# MotorController.net
KiCad netlist of a schematic drawn in Altium Designer
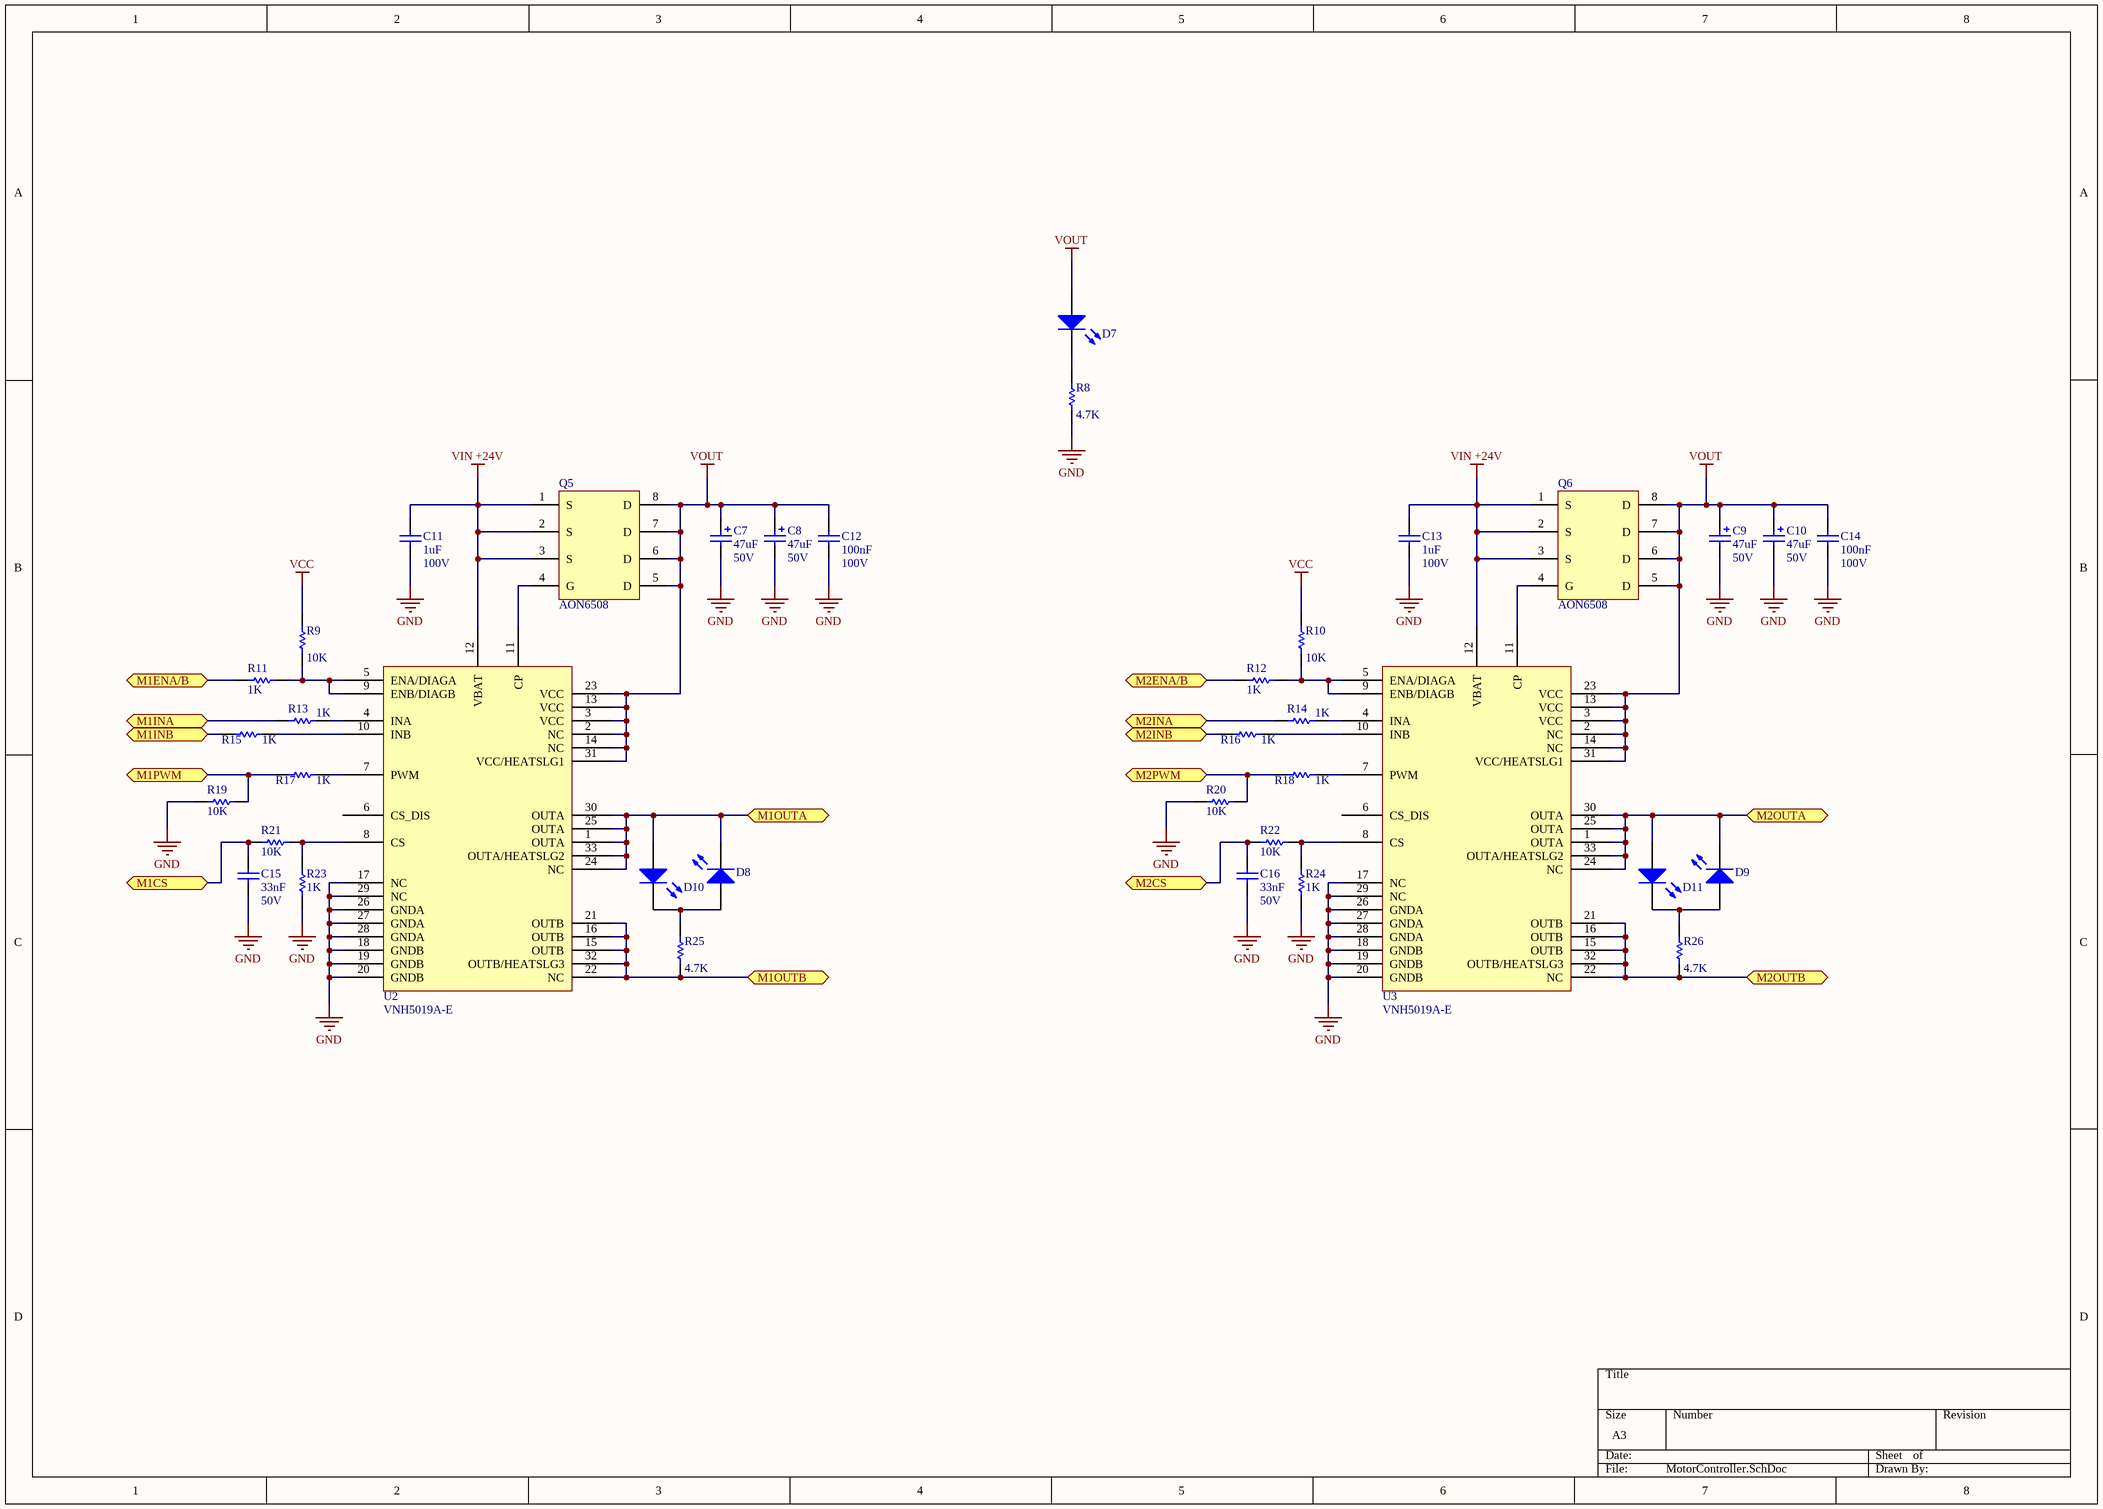
[diagram p0: MotorController.SchDoc]

(export (version "E")
  (design (tool "Eeschema 10.0.6"))
  (components
    (comp (ref "C7")
      (value "47uF")
      (footprint "CAP D Size")
      (description "Polarized Capacitor (Radial)")
      (fields
        (field (name "VOLTAGE") "50V")
        (field (name "Comment") "Cap Pol1")
        (field (name "PUBLISHER") "Altium Limited")
      )
      (libsource (lib "Erdem_05112012") (part "Cap Pol1"))
    )
    (comp (ref "C8")
      (value "47uF")
      (footprint "CAP D Size")
      (description "Polarized Capacitor (Radial)")
      (fields
        (field (name "VOLTAGE") "50V")
        (field (name "Comment") "Cap Pol1")
        (field (name "PUBLISHER") "Altium Limited")
      )
      (libsource (lib "Erdem_05112012") (part "Cap Pol1"))
    )
    (comp (ref "C9")
      (value "47uF")
      (footprint "CAP D Size")
      (description "Polarized Capacitor (Radial)")
      (fields
        (field (name "VOLTAGE") "50V")
        (field (name "Comment") "Cap Pol1")
        (field (name "PUBLISHER") "Altium Limited")
      )
      (libsource (lib "Erdem_05112012") (part "Cap Pol1"))
    )
    (comp (ref "C10")
      (value "47uF")
      (footprint "CAP D Size")
      (description "Polarized Capacitor (Radial)")
      (fields
        (field (name "VOLTAGE") "50V")
        (field (name "Comment") "Cap Pol1")
        (field (name "PUBLISHER") "Altium Limited")
      )
      (libsource (lib "Erdem_05112012") (part "Cap Pol1"))
    )
    (comp (ref "C11")
      (value "1uF")
      (footprint "8-1206")
      (description "Capacitor")
      (fields
        (field (name "VOLTAGE") "100V")
        (field (name "Comment") "Cap")
        (field (name "PUBLISHER") "Altium Limited")
      )
      (libsource (lib "Erdem_05112012") (part "Cap"))
    )
    (comp (ref "C12")
      (value "100nF")
      (footprint "6-0805 - big")
      (description "Capacitor")
      (fields
        (field (name "VOLTAGE") "100V")
        (field (name "Comment") "Cap")
        (field (name "PUBLISHER") "Altium Limited")
      )
      (libsource (lib "Erdem_05112012") (part "Cap"))
    )
    (comp (ref "C13")
      (value "1uF")
      (footprint "8-1206")
      (description "Capacitor")
      (fields
        (field (name "VOLTAGE") "100V")
        (field (name "Comment") "Cap")
        (field (name "PUBLISHER") "Altium Limited")
      )
      (libsource (lib "Erdem_05112012") (part "Cap"))
    )
    (comp (ref "C14")
      (value "100nF")
      (footprint "6-0805 - big")
      (description "Capacitor")
      (fields
        (field (name "VOLTAGE") "100V")
        (field (name "Comment") "Cap")
        (field (name "PUBLISHER") "Altium Limited")
      )
      (libsource (lib "Erdem_05112012") (part "Cap"))
    )
    (comp (ref "C15")
      (value "33nF")
      (footprint "3-0603_L")
      (description "Capacitor")
      (fields
        (field (name "VOLTAGE") "50V")
        (field (name "Comment") "Cap")
        (field (name "PUBLISHER") "Altium Limited")
      )
      (libsource (lib "Erdem_05112012") (part "Cap"))
    )
    (comp (ref "C16")
      (value "33nF")
      (footprint "3-0603_L")
      (description "Capacitor")
      (fields
        (field (name "VOLTAGE") "50V")
        (field (name "Comment") "Cap")
        (field (name "PUBLISHER") "Altium Limited")
      )
      (libsource (lib "Erdem_05112012") (part "Cap"))
    )
    (comp (ref "D7")
      (value "LED")
      (footprint "6-0805 - LED")
      (description "Typical INFRARED GaAs LED")
      (fields (field (name "PUBLISHER") "Altium Limited"))
      (libsource (lib "Erdem_05112012") (part "LED"))
    )
    (comp (ref "D8")
      (value "LED")
      (footprint "6-0805 - LED")
      (description "Typical INFRARED GaAs LED")
      (fields (field (name "PUBLISHER") "Altium Limited"))
      (libsource (lib "Erdem_05112012") (part "LED"))
    )
    (comp (ref "D9")
      (value "LED")
      (footprint "6-0805 - LED")
      (description "Typical INFRARED GaAs LED")
      (fields (field (name "PUBLISHER") "Altium Limited"))
      (libsource (lib "Erdem_05112012") (part "LED"))
    )
    (comp (ref "D10")
      (value "LED")
      (footprint "6-0805 - LED")
      (description "Typical INFRARED GaAs LED")
      (fields (field (name "PUBLISHER") "Altium Limited"))
      (libsource (lib "Erdem_05112012") (part "LED"))
    )
    (comp (ref "D11")
      (value "LED")
      (footprint "6-0805 - LED")
      (description "Typical INFRARED GaAs LED")
      (fields (field (name "PUBLISHER") "Altium Limited"))
      (libsource (lib "Erdem_05112012") (part "LED"))
    )
    (comp (ref "Q5")
      (value "AON6508")
      (footprint "DFN5x6 EP")
      (description "30V N-Channel AlphaMOS")
      (fields (field (name "PUBLISHER") "Altium Limited"))
      (libsource (lib "Erdem_05112012") (part "AON6508"))
    )
    (comp (ref "Q6")
      (value "AON6508")
      (footprint "DFN5x6 EP")
      (description "30V N-Channel AlphaMOS")
      (fields (field (name "PUBLISHER") "Altium Limited"))
      (libsource (lib "Erdem_05112012") (part "AON6508"))
    )
    (comp (ref "R8")
      (value "4.7K")
      (footprint "3-0603_L")
      (description "Resistor")
      (fields (field (name "Comment") "Res1") (field (name "PUBLISHER") "Altium Limited"))
      (libsource (lib "Erdem_05112012") (part "Res1"))
    )
    (comp (ref "R9")
      (value "10K")
      (footprint "3-0603_L")
      (description "Resistor")
      (fields (field (name "Comment") "Res1") (field (name "PUBLISHER") "Altium Limited"))
      (libsource (lib "Erdem_05112012") (part "Res1"))
    )
    (comp (ref "R10")
      (value "10K")
      (footprint "3-0603_L")
      (description "Resistor")
      (fields (field (name "Comment") "Res1") (field (name "PUBLISHER") "Altium Limited"))
      (libsource (lib "Erdem_05112012") (part "Res1"))
    )
    (comp (ref "R11")
      (value "1K")
      (footprint "3-0603_L")
      (description "Resistor")
      (fields (field (name "Comment") "Res1") (field (name "PUBLISHER") "Altium Limited"))
      (libsource (lib "Erdem_05112012") (part "Res1"))
    )
    (comp (ref "R12")
      (value "1K")
      (footprint "3-0603_L")
      (description "Resistor")
      (fields (field (name "Comment") "Res1") (field (name "PUBLISHER") "Altium Limited"))
      (libsource (lib "Erdem_05112012") (part "Res1"))
    )
    (comp (ref "R13")
      (value "1K")
      (footprint "3-0603_L")
      (description "Resistor")
      (fields (field (name "Comment") "Res1") (field (name "PUBLISHER") "Altium Limited"))
      (libsource (lib "Erdem_05112012") (part "Res1"))
    )
    (comp (ref "R14")
      (value "1K")
      (footprint "3-0603_L")
      (description "Resistor")
      (fields (field (name "Comment") "Res1") (field (name "PUBLISHER") "Altium Limited"))
      (libsource (lib "Erdem_05112012") (part "Res1"))
    )
    (comp (ref "R15")
      (value "1K")
      (footprint "3-0603_L")
      (description "Resistor")
      (fields (field (name "Comment") "Res1") (field (name "PUBLISHER") "Altium Limited"))
      (libsource (lib "Erdem_05112012") (part "Res1"))
    )
    (comp (ref "R16")
      (value "1K")
      (footprint "3-0603_L")
      (description "Resistor")
      (fields (field (name "Comment") "Res1") (field (name "PUBLISHER") "Altium Limited"))
      (libsource (lib "Erdem_05112012") (part "Res1"))
    )
    (comp (ref "R17")
      (value "1K")
      (footprint "3-0603_L")
      (description "Resistor")
      (fields (field (name "Comment") "Res1") (field (name "PUBLISHER") "Altium Limited"))
      (libsource (lib "Erdem_05112012") (part "Res1"))
    )
    (comp (ref "R18")
      (value "1K")
      (footprint "3-0603_L")
      (description "Resistor")
      (fields (field (name "Comment") "Res1") (field (name "PUBLISHER") "Altium Limited"))
      (libsource (lib "Erdem_05112012") (part "Res1"))
    )
    (comp (ref "R19")
      (value "10K")
      (footprint "3-0603_L")
      (description "Resistor")
      (fields (field (name "Comment") "Res1") (field (name "PUBLISHER") "Altium Limited"))
      (libsource (lib "Erdem_05112012") (part "Res1"))
    )
    (comp (ref "R20")
      (value "10K")
      (footprint "3-0603_L")
      (description "Resistor")
      (fields (field (name "Comment") "Res1") (field (name "PUBLISHER") "Altium Limited"))
      (libsource (lib "Erdem_05112012") (part "Res1"))
    )
    (comp (ref "R21")
      (value "10K")
      (footprint "3-0603_L")
      (description "Resistor")
      (fields (field (name "Comment") "Res1") (field (name "PUBLISHER") "Altium Limited"))
      (libsource (lib "Erdem_05112012") (part "Res1"))
    )
    (comp (ref "R22")
      (value "10K")
      (footprint "3-0603_L")
      (description "Resistor")
      (fields (field (name "Comment") "Res1") (field (name "PUBLISHER") "Altium Limited"))
      (libsource (lib "Erdem_05112012") (part "Res1"))
    )
    (comp (ref "R23")
      (value "1K")
      (footprint "3-0603_L")
      (description "Resistor")
      (fields (field (name "Comment") "Res1") (field (name "PUBLISHER") "Altium Limited"))
      (libsource (lib "Erdem_05112012") (part "Res1"))
    )
    (comp (ref "R24")
      (value "1K")
      (footprint "3-0603_L")
      (description "Resistor")
      (fields (field (name "Comment") "Res1") (field (name "PUBLISHER") "Altium Limited"))
      (libsource (lib "Erdem_05112012") (part "Res1"))
    )
    (comp (ref "R25")
      (value "4.7K")
      (footprint "3-0603_L")
      (description "Resistor")
      (fields (field (name "Comment") "Res1") (field (name "PUBLISHER") "Altium Limited"))
      (libsource (lib "Erdem_05112012") (part "Res1"))
    )
    (comp (ref "R26")
      (value "4.7K")
      (footprint "3-0603_L")
      (description "Resistor")
      (fields (field (name "Comment") "Res1") (field (name "PUBLISHER") "Altium Limited"))
      (libsource (lib "Erdem_05112012") (part "Res1"))
    )
    (comp (ref "U2")
      (value "VNH5019A-E")
      (footprint "MultiPowerSO-30")
      (description "Automotive fully integrated H-bridge motor driver")
      (fields (field (name "PUBLISHER") "Altium Limited"))
      (libsource (lib "Erdem_05112012") (part "VNH5019A-E"))
    )
    (comp (ref "U3")
      (value "VNH5019A-E")
      (footprint "MultiPowerSO-30")
      (description "Automotive fully integrated H-bridge motor driver")
      (fields (field (name "PUBLISHER") "Altium Limited"))
      (libsource (lib "Erdem_05112012") (part "VNH5019A-E"))
    )
  )
  (nets
    (net (code "1") (name "/M1CS") (class "Default")
      (node (ref "C15") (pin "2") (pinfunction "2_2") (pintype "passive"))
      (node (ref "R21") (pin "2") (pinfunction "2_2") (pintype "passive"))
    )
    (net (code "2") (name "/M1ENA{slash}B") (class "Default")
      (node (ref "R11") (pin "1") (pinfunction "1_1") (pintype "passive"))
    )
    (net (code "3") (name "/M1INA") (class "Default")
      (node (ref "R13") (pin "1") (pinfunction "1_1") (pintype "passive"))
    )
    (net (code "4") (name "/M1INB") (class "Default")
      (node (ref "R15") (pin "1") (pinfunction "1_1") (pintype "passive"))
    )
    (net (code "5") (name "/M1OUTA") (class "Default")
      (node (ref "D10") (pin "1") (pinfunction "A_1") (pintype "passive"))
      (node (ref "D8") (pin "2") (pinfunction "K_2") (pintype "passive"))
      (node (ref "U2") (pin "1") (pinfunction "OUTA_1") (pintype "passive"))
      (node (ref "U2") (pin "24") (pinfunction "NC_24") (pintype "passive"))
      (node (ref "U2") (pin "25") (pinfunction "OUTA_25") (pintype "passive"))
      (node (ref "U2") (pin "30") (pinfunction "OUTA_30") (pintype "passive"))
      (node (ref "U2") (pin "33") (pinfunction "OUTA/HEATSLG2_33") (pintype "passive"))
    )
    (net (code "6") (name "/M1OUTB") (class "Default")
      (node (ref "R25") (pin "1") (pinfunction "1_1") (pintype "passive"))
      (node (ref "U2") (pin "15") (pinfunction "OUTB_15") (pintype "passive"))
      (node (ref "U2") (pin "16") (pinfunction "OUTB_16") (pintype "passive"))
      (node (ref "U2") (pin "21") (pinfunction "OUTB_21") (pintype "passive"))
      (node (ref "U2") (pin "22") (pinfunction "NC_22") (pintype "passive"))
      (node (ref "U2") (pin "32") (pinfunction "OUTB/HEATSLG3_32") (pintype "passive"))
    )
    (net (code "7") (name "/M1PWM") (class "Default")
      (node (ref "R17") (pin "1") (pinfunction "1_1") (pintype "passive"))
      (node (ref "R19") (pin "2") (pinfunction "2_2") (pintype "passive"))
    )
    (net (code "8") (name "/M2CS") (class "Default")
      (node (ref "C16") (pin "2") (pinfunction "2_2") (pintype "passive"))
      (node (ref "R22") (pin "2") (pinfunction "2_2") (pintype "passive"))
    )
    (net (code "9") (name "/M2ENA{slash}B") (class "Default")
      (node (ref "R12") (pin "1") (pinfunction "1_1") (pintype "passive"))
    )
    (net (code "10") (name "/M2INA") (class "Default")
      (node (ref "R14") (pin "1") (pinfunction "1_1") (pintype "passive"))
    )
    (net (code "11") (name "/M2INB") (class "Default")
      (node (ref "R16") (pin "1") (pinfunction "1_1") (pintype "passive"))
    )
    (net (code "12") (name "/M2OUTA") (class "Default")
      (node (ref "D11") (pin "1") (pinfunction "A_1") (pintype "passive"))
      (node (ref "D9") (pin "2") (pinfunction "K_2") (pintype "passive"))
      (node (ref "U3") (pin "1") (pinfunction "OUTA_1") (pintype "passive"))
      (node (ref "U3") (pin "24") (pinfunction "NC_24") (pintype "passive"))
      (node (ref "U3") (pin "25") (pinfunction "OUTA_25") (pintype "passive"))
      (node (ref "U3") (pin "30") (pinfunction "OUTA_30") (pintype "passive"))
      (node (ref "U3") (pin "33") (pinfunction "OUTA/HEATSLG2_33") (pintype "passive"))
    )
    (net (code "13") (name "/M2OUTB") (class "Default")
      (node (ref "R26") (pin "1") (pinfunction "1_1") (pintype "passive"))
      (node (ref "U3") (pin "15") (pinfunction "OUTB_15") (pintype "passive"))
      (node (ref "U3") (pin "16") (pinfunction "OUTB_16") (pintype "passive"))
      (node (ref "U3") (pin "21") (pinfunction "OUTB_21") (pintype "passive"))
      (node (ref "U3") (pin "22") (pinfunction "NC_22") (pintype "passive"))
      (node (ref "U3") (pin "32") (pinfunction "OUTB/HEATSLG3_32") (pintype "passive"))
    )
    (net (code "14") (name "/M2PWM") (class "Default")
      (node (ref "R18") (pin "1") (pinfunction "1_1") (pintype "passive"))
      (node (ref "R20") (pin "2") (pinfunction "2_2") (pintype "passive"))
    )
    (net (code "15") (name "GND") (class "Default")
      (node (ref "C10") (pin "2") (pinfunction "2_2") (pintype "passive"))
      (node (ref "C11") (pin "1") (pinfunction "1_1") (pintype "passive"))
      (node (ref "C12") (pin "1") (pinfunction "1_1") (pintype "passive"))
      (node (ref "C13") (pin "1") (pinfunction "1_1") (pintype "passive"))
      (node (ref "C14") (pin "1") (pinfunction "1_1") (pintype "passive"))
      (node (ref "C15") (pin "1") (pinfunction "1_1") (pintype "passive"))
      (node (ref "C16") (pin "1") (pinfunction "1_1") (pintype "passive"))
      (node (ref "C7") (pin "2") (pinfunction "2_2") (pintype "passive"))
      (node (ref "C8") (pin "2") (pinfunction "2_2") (pintype "passive"))
      (node (ref "C9") (pin "2") (pinfunction "2_2") (pintype "passive"))
      (node (ref "R19") (pin "1") (pinfunction "1_1") (pintype "passive"))
      (node (ref "R20") (pin "1") (pinfunction "1_1") (pintype "passive"))
      (node (ref "R23") (pin "1") (pinfunction "1_1") (pintype "passive"))
      (node (ref "R24") (pin "1") (pinfunction "1_1") (pintype "passive"))
      (node (ref "R8") (pin "1") (pinfunction "1_1") (pintype "passive"))
      (node (ref "U2") (pin "17") (pinfunction "NC_17") (pintype "passive"))
      (node (ref "U2") (pin "18") (pinfunction "GNDB_18") (pintype "passive"))
      (node (ref "U2") (pin "19") (pinfunction "GNDB_19") (pintype "passive"))
      (node (ref "U2") (pin "20") (pinfunction "GNDB_20") (pintype "passive"))
      (node (ref "U2") (pin "26") (pinfunction "GNDA_26") (pintype "passive"))
      (node (ref "U2") (pin "27") (pinfunction "GNDA_27") (pintype "passive"))
      (node (ref "U2") (pin "28") (pinfunction "GNDA_28") (pintype "passive"))
      (node (ref "U2") (pin "29") (pinfunction "NC_29") (pintype "passive"))
      (node (ref "U3") (pin "17") (pinfunction "NC_17") (pintype "passive"))
      (node (ref "U3") (pin "18") (pinfunction "GNDB_18") (pintype "passive"))
      (node (ref "U3") (pin "19") (pinfunction "GNDB_19") (pintype "passive"))
      (node (ref "U3") (pin "20") (pinfunction "GNDB_20") (pintype "passive"))
      (node (ref "U3") (pin "26") (pinfunction "GNDA_26") (pintype "passive"))
      (node (ref "U3") (pin "27") (pinfunction "GNDA_27") (pintype "passive"))
      (node (ref "U3") (pin "28") (pinfunction "GNDA_28") (pintype "passive"))
      (node (ref "U3") (pin "29") (pinfunction "NC_29") (pintype "passive"))
    )
    (net (code "16") (name "Net-(D7-K)") (class "Default")
      (node (ref "D7") (pin "2") (pinfunction "K_2") (pintype "passive"))
      (node (ref "R8") (pin "2") (pinfunction "2_2") (pintype "passive"))
    )
    (net (code "17") (name "Net-(D10-K)") (class "Default")
      (node (ref "D10") (pin "2") (pinfunction "K_2") (pintype "passive"))
      (node (ref "D8") (pin "1") (pinfunction "A_1") (pintype "passive"))
      (node (ref "R25") (pin "2") (pinfunction "2_2") (pintype "passive"))
    )
    (net (code "18") (name "Net-(D11-K)") (class "Default")
      (node (ref "D11") (pin "2") (pinfunction "K_2") (pintype "passive"))
      (node (ref "D9") (pin "1") (pinfunction "A_1") (pintype "passive"))
      (node (ref "R26") (pin "2") (pinfunction "2_2") (pintype "passive"))
    )
    (net (code "19") (name "Net-(Q5-G)") (class "Default")
      (node (ref "Q5") (pin "4") (pinfunction "G_4") (pintype "passive"))
      (node (ref "U2") (pin "11") (pinfunction "CP_11") (pintype "passive"))
    )
    (net (code "20") (name "Net-(Q6-G)") (class "Default")
      (node (ref "Q6") (pin "4") (pinfunction "G_4") (pintype "passive"))
      (node (ref "U3") (pin "11") (pinfunction "CP_11") (pintype "passive"))
    )
    (net (code "21") (name "Net-(U2-CS)") (class "Default")
      (node (ref "R21") (pin "1") (pinfunction "1_1") (pintype "passive"))
      (node (ref "R23") (pin "2") (pinfunction "2_2") (pintype "passive"))
      (node (ref "U2") (pin "8") (pinfunction "CS_8") (pintype "passive"))
    )
    (net (code "22") (name "Net-(U2-ENA{slash}DIAGA)") (class "Default")
      (node (ref "R11") (pin "2") (pinfunction "2_2") (pintype "passive"))
      (node (ref "R9") (pin "1") (pinfunction "1_1") (pintype "passive"))
      (node (ref "U2") (pin "5") (pinfunction "ENA/DIAGA_5") (pintype "passive"))
      (node (ref "U2") (pin "9") (pinfunction "ENB/DIAGB_9") (pintype "passive"))
    )
    (net (code "23") (name "Net-(U2-INA)") (class "Default")
      (node (ref "R13") (pin "2") (pinfunction "2_2") (pintype "passive"))
      (node (ref "U2") (pin "4") (pinfunction "INA_4") (pintype "passive"))
    )
    (net (code "24") (name "Net-(U2-INB)") (class "Default")
      (node (ref "R15") (pin "2") (pinfunction "2_2") (pintype "passive"))
      (node (ref "U2") (pin "10") (pinfunction "INB_10") (pintype "passive"))
    )
    (net (code "25") (name "Net-(U2-PWM)") (class "Default")
      (node (ref "R17") (pin "2") (pinfunction "2_2") (pintype "passive"))
      (node (ref "U2") (pin "7") (pinfunction "PWM_7") (pintype "passive"))
    )
    (net (code "26") (name "Net-(U3-CS)") (class "Default")
      (node (ref "R22") (pin "1") (pinfunction "1_1") (pintype "passive"))
      (node (ref "R24") (pin "2") (pinfunction "2_2") (pintype "passive"))
      (node (ref "U3") (pin "8") (pinfunction "CS_8") (pintype "passive"))
    )
    (net (code "27") (name "Net-(U3-ENA{slash}DIAGA)") (class "Default")
      (node (ref "R10") (pin "1") (pinfunction "1_1") (pintype "passive"))
      (node (ref "R12") (pin "2") (pinfunction "2_2") (pintype "passive"))
      (node (ref "U3") (pin "5") (pinfunction "ENA/DIAGA_5") (pintype "passive"))
      (node (ref "U3") (pin "9") (pinfunction "ENB/DIAGB_9") (pintype "passive"))
    )
    (net (code "28") (name "Net-(U3-INA)") (class "Default")
      (node (ref "R14") (pin "2") (pinfunction "2_2") (pintype "passive"))
      (node (ref "U3") (pin "4") (pinfunction "INA_4") (pintype "passive"))
    )
    (net (code "29") (name "Net-(U3-INB)") (class "Default")
      (node (ref "R16") (pin "2") (pinfunction "2_2") (pintype "passive"))
      (node (ref "U3") (pin "10") (pinfunction "INB_10") (pintype "passive"))
    )
    (net (code "30") (name "Net-(U3-PWM)") (class "Default")
      (node (ref "R18") (pin "2") (pinfunction "2_2") (pintype "passive"))
      (node (ref "U3") (pin "7") (pinfunction "PWM_7") (pintype "passive"))
    )
    (net (code "31") (name "VCC") (class "Default")
      (node (ref "R10") (pin "2") (pinfunction "2_2") (pintype "passive"))
      (node (ref "R9") (pin "2") (pinfunction "2_2") (pintype "passive"))
    )
    (net (code "32") (name "VIN +24V") (class "Default")
      (node (ref "C11") (pin "2") (pinfunction "2_2") (pintype "passive"))
      (node (ref "C13") (pin "2") (pinfunction "2_2") (pintype "passive"))
      (node (ref "Q5") (pin "1") (pinfunction "S_1") (pintype "passive"))
      (node (ref "Q5") (pin "2") (pinfunction "S_2") (pintype "passive"))
      (node (ref "Q5") (pin "3") (pinfunction "S_3") (pintype "passive"))
      (node (ref "Q6") (pin "1") (pinfunction "S_1") (pintype "passive"))
      (node (ref "Q6") (pin "2") (pinfunction "S_2") (pintype "passive"))
      (node (ref "Q6") (pin "3") (pinfunction "S_3") (pintype "passive"))
      (node (ref "U2") (pin "12") (pinfunction "VBAT_12") (pintype "passive"))
      (node (ref "U3") (pin "12") (pinfunction "VBAT_12") (pintype "passive"))
    )
    (net (code "33") (name "VOUT") (class "Default")
      (node (ref "C10") (pin "1") (pinfunction "1_1") (pintype "passive"))
      (node (ref "C12") (pin "2") (pinfunction "2_2") (pintype "passive"))
      (node (ref "C14") (pin "2") (pinfunction "2_2") (pintype "passive"))
      (node (ref "C7") (pin "1") (pinfunction "1_1") (pintype "passive"))
      (node (ref "C8") (pin "1") (pinfunction "1_1") (pintype "passive"))
      (node (ref "C9") (pin "1") (pinfunction "1_1") (pintype "passive"))
      (node (ref "D7") (pin "1") (pinfunction "A_1") (pintype "passive"))
      (node (ref "Q5") (pin "5") (pinfunction "D_5") (pintype "passive"))
      (node (ref "Q5") (pin "6") (pinfunction "D_6") (pintype "passive"))
      (node (ref "Q5") (pin "7") (pinfunction "D_7") (pintype "passive"))
      (node (ref "Q5") (pin "8") (pinfunction "D_8") (pintype "passive"))
      (node (ref "Q6") (pin "5") (pinfunction "D_5") (pintype "passive"))
      (node (ref "Q6") (pin "6") (pinfunction "D_6") (pintype "passive"))
      (node (ref "Q6") (pin "7") (pinfunction "D_7") (pintype "passive"))
      (node (ref "Q6") (pin "8") (pinfunction "D_8") (pintype "passive"))
      (node (ref "U2") (pin "13") (pinfunction "VCC_13") (pintype "passive"))
      (node (ref "U2") (pin "14") (pinfunction "NC_14") (pintype "passive"))
      (node (ref "U2") (pin "2") (pinfunction "NC_2") (pintype "passive"))
      (node (ref "U2") (pin "23") (pinfunction "VCC_23") (pintype "passive"))
      (node (ref "U2") (pin "3") (pinfunction "VCC_3") (pintype "passive"))
      (node (ref "U2") (pin "31") (pinfunction "VCC/HEATSLG1_31") (pintype "passive"))
      (node (ref "U3") (pin "13") (pinfunction "VCC_13") (pintype "passive"))
      (node (ref "U3") (pin "14") (pinfunction "NC_14") (pintype "passive"))
      (node (ref "U3") (pin "2") (pinfunction "NC_2") (pintype "passive"))
      (node (ref "U3") (pin "23") (pinfunction "VCC_23") (pintype "passive"))
      (node (ref "U3") (pin "3") (pinfunction "VCC_3") (pintype "passive"))
      (node (ref "U3") (pin "31") (pinfunction "VCC/HEATSLG1_31") (pintype "passive"))
    )
    (net (code "34") (name "unconnected-(U2-CS_DIS-Pad6)") (class "Default")
      (node (ref "U2") (pin "6") (pinfunction "CS_DIS_6") (pintype "passive"))
    )
    (net (code "35") (name "unconnected-(U3-CS_DIS-Pad6)") (class "Default")
      (node (ref "U3") (pin "6") (pinfunction "CS_DIS_6") (pintype "passive"))
    )
  )
)
